# Weatstone_bridges_part_II.net
KiCad netlist of a schematic drawn in Altium Designer
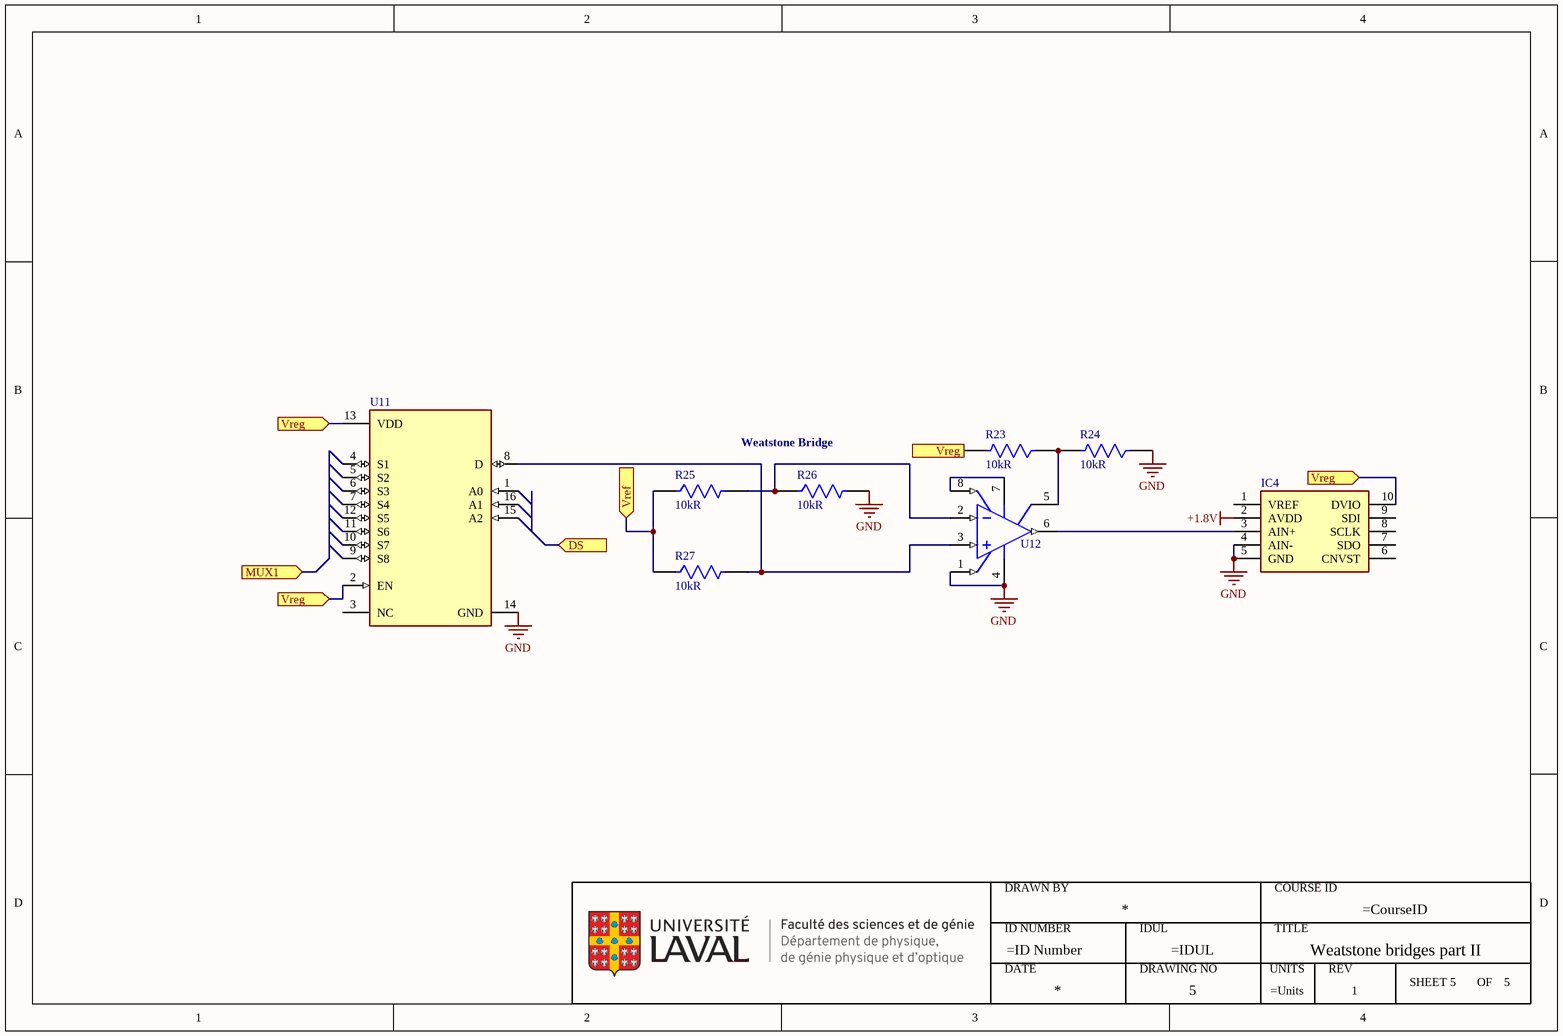
[diagram p0: Weatstone bridges part II.SchDoc]

(export (version "E")
  (design (tool "Eeschema 10.0.6"))
  (components
    (comp (ref "*4")
      (value "ULaval FSG-DPGPO")
      (libsource (lib "ULaval Title Block") (part "ULaval FSG-DPGPO"))
    )
    (comp (ref "IC4")
      (value "MCP33141-10-E_MS")
      (footprint "SamacSys:SOP50P490X110-10N")
      (description "Integrated Circuit")
      (fields
        (field (name "MANUFACTURER_PART_NUMBER") "MCP33141-10-E/MS")
        (field (name "MOUSER PART NUMBER") "579-MCP33141-10-E/MS")
      )
      (libsource (lib "SamacSys") (part "MCP33141-10-E_MS"))
    )
    (comp (ref "R23")
      (value "10kR")
      (footprint "FP-RT0603-IPC_C")
      (description "Res High precision Thin Film 0603 10K Ohm 0.1% 1/10W ±25ppm/°C Molded SMD Paper T/R")
      (fields (field (name "Comment") "RT0603BRD0710KL"))
      (libsource (lib "Laval University") (part "1029c3af85768c4190bb7ad29bc67b5"))
    )
    (comp (ref "R24")
      (value "10kR")
      (footprint "FP-RT0603-IPC_C")
      (description "Res High precision Thin Film 0603 10K Ohm 0.1% 1/10W ±25ppm/°C Molded SMD Paper T/R")
      (fields (field (name "Comment") "RT0603BRD0710KL"))
      (libsource (lib "Laval University") (part "1029c3af85768c4190bb7ad29bc67b5"))
    )
    (comp (ref "R25")
      (value "10kR")
      (footprint "FP-RT0603-IPC_C")
      (description "Res High precision Thin Film 0603 10K Ohm 0.1% 1/10W ±25ppm/°C Molded SMD Paper T/R")
      (fields (field (name "Comment") "RT0603BRD0710KL"))
      (libsource (lib "Laval University") (part "1029c3af85768c4190bb7ad29bc67b5"))
    )
    (comp (ref "R26")
      (value "10kR")
      (footprint "FP-RT0603-IPC_C")
      (description "Res High precision Thin Film 0603 10K Ohm 0.1% 1/10W ±25ppm/°C Molded SMD Paper T/R")
      (fields (field (name "Comment") "RT0603BRD0710KL"))
      (libsource (lib "Laval University") (part "1029c3af85768c4190bb7ad29bc67b5"))
    )
    (comp (ref "R27")
      (value "10kR")
      (footprint "FP-RT0603-IPC_C")
      (description "Res High precision Thin Film 0603 10K Ohm 0.1% 1/10W ±25ppm/°C Molded SMD Paper T/R")
      (fields (field (name "Comment") "RT0603BRD0710KL"))
      (libsource (lib "Laval University") (part "1029c3af85768c4190bb7ad29bc67b5"))
    )
    (comp (ref "U11")
      (value "TMUX1208PWR")
      (footprint "FP-PW0016A-IPC_B")
      (description "5-V, 8: 1, 1-channel general-purpose analog multiplexer with 1.8-V input logic 16-TSSOP -40 to 125")
      (libsource (lib "Laval University") (part "3fc1eebd4caa5623a46538ca285a60d"))
    )
    (comp (ref "U12")
      (value "MCP6N11-100E/SN")
      (footprint "SOIC-SN8_L")
      (description "MCP6N11 Series Single Channel 500 KHz 5.5 V Instrumentation Amplifier - SOIC-8")
      (libsource (lib "Laval University") (part "AMP-INA-MCP6N11-IL8"))
    )
  )
  (nets
    (net (code "1") (name "+1.8V") (class "Default")
      (node (ref "IC4") (pin "2") (pinfunction "AVDD_2") (pintype "passive"))
    )
    (net (code "4") (name "/Vref") (class "Default")
      (node (ref "R25") (pin "1") (pinfunction "1_1") (pintype "passive"))
      (node (ref "R27") (pin "1") (pinfunction "1_1") (pintype "passive"))
    )
    (net (code "5") (name "/Vreg") (class "Default")
      (node (ref "IC4") (pin "10") (pinfunction "DVIO_10") (pintype "passive"))
      (node (ref "R23") (pin "2") (pinfunction "2_2") (pintype "passive"))
      (node (ref "U11") (pin "13") (pinfunction "VDD_13") (pintype "power_in"))
      (node (ref "U11") (pin "2") (pinfunction "EN_2") (pintype "input"))
    )
    (net (code "6") (name "GND") (class "Default")
      (node (ref "IC4") (pin "4") (pinfunction "AIN-_4") (pintype "passive"))
      (node (ref "IC4") (pin "5") (pinfunction "GND_5") (pintype "passive"))
      (node (ref "R24") (pin "1") (pinfunction "1_1") (pintype "passive"))
      (node (ref "R26") (pin "2") (pinfunction "2_2") (pintype "passive"))
      (node (ref "U11") (pin "14") (pinfunction "GND_14") (pintype "power_in"))
      (node (ref "U12") (pin "1") (pinfunction "VFG_1") (pintype "input"))
      (node (ref "U12") (pin "4") (pinfunction "VSS_4") (pintype "power_in"))
    )
    (net (code "7") (name "Net-(IC4-AIN+)") (class "Default")
      (node (ref "IC4") (pin "3") (pinfunction "AIN+_3") (pintype "passive"))
      (node (ref "U12") (pin "6") (pinfunction "VOUT_6") (pintype "output"))
    )
    (net (code "8") (name "Net-(U11-D)") (class "Default")
      (node (ref "R27") (pin "2") (pinfunction "2_2") (pintype "passive"))
      (node (ref "U11") (pin "8") (pinfunction "D_8") (pintype "bidirectional"))
      (node (ref "U12") (pin "3") (pinfunction "VIP_3") (pintype "input"))
    )
    (net (code "9") (name "Net-(U12-EN{slash}~{CAL})") (class "Default")
      (node (ref "U12") (pin "7") (pinfunction "VDD_7") (pintype "power_in"))
      (node (ref "U12") (pin "8") (pinfunction "EN/~{CAL}_8") (pintype "input"))
    )
    (net (code "10") (name "Net-(U12-VIM)") (class "Default")
      (node (ref "R25") (pin "2") (pinfunction "2_2") (pintype "passive"))
      (node (ref "R26") (pin "1") (pinfunction "1_1") (pintype "passive"))
      (node (ref "U12") (pin "2") (pinfunction "VIM_2") (pintype "input"))
    )
    (net (code "11") (name "Net-(U12-VREF)") (class "Default")
      (node (ref "R23") (pin "1") (pinfunction "1_1") (pintype "passive"))
      (node (ref "R24") (pin "2") (pinfunction "2_2") (pintype "passive"))
      (node (ref "U12") (pin "5") (pinfunction "VREF_5") (pintype "power_in"))
    )
    (net (code "12") (name "unconnected-(IC4-CNVST-Pad6)") (class "Default")
      (node (ref "IC4") (pin "6") (pinfunction "CNVST_6") (pintype "passive"))
    )
    (net (code "13") (name "unconnected-(IC4-SCLK-Pad8)") (class "Default")
      (node (ref "IC4") (pin "8") (pinfunction "SCLK_8") (pintype "passive"))
    )
    (net (code "14") (name "unconnected-(IC4-SDI-Pad9)") (class "Default")
      (node (ref "IC4") (pin "9") (pinfunction "SDI_9") (pintype "passive"))
    )
    (net (code "15") (name "unconnected-(IC4-SDO-Pad7)") (class "Default")
      (node (ref "IC4") (pin "7") (pinfunction "SDO_7") (pintype "passive"))
    )
    (net (code "16") (name "unconnected-(IC4-VREF-Pad1)") (class "Default")
      (node (ref "IC4") (pin "1") (pinfunction "VREF_1") (pintype "passive"))
    )
    (net (code "17") (name "unconnected-(U11-A0-Pad1)") (class "Default")
      (node (ref "U11") (pin "1") (pinfunction "A0_1") (pintype "input"))
    )
    (net (code "18") (name "unconnected-(U11-A1-Pad16)") (class "Default")
      (node (ref "U11") (pin "16") (pinfunction "A1_16") (pintype "input"))
    )
    (net (code "19") (name "unconnected-(U11-A2-Pad15)") (class "Default")
      (node (ref "U11") (pin "15") (pinfunction "A2_15") (pintype "input"))
    )
    (net (code "20") (name "unconnected-(U11-NC-Pad3)") (class "Default")
      (node (ref "U11") (pin "3") (pinfunction "NC_3") (pintype "passive"))
    )
    (net (code "21") (name "unconnected-(U11-S1-Pad4)") (class "Default")
      (node (ref "U11") (pin "4") (pinfunction "S1_4") (pintype "bidirectional"))
    )
    (net (code "22") (name "unconnected-(U11-S2-Pad5)") (class "Default")
      (node (ref "U11") (pin "5") (pinfunction "S2_5") (pintype "bidirectional"))
    )
    (net (code "23") (name "unconnected-(U11-S3-Pad6)") (class "Default")
      (node (ref "U11") (pin "6") (pinfunction "S3_6") (pintype "bidirectional"))
    )
    (net (code "24") (name "unconnected-(U11-S4-Pad7)") (class "Default")
      (node (ref "U11") (pin "7") (pinfunction "S4_7") (pintype "bidirectional"))
    )
    (net (code "25") (name "unconnected-(U11-S5-Pad12)") (class "Default")
      (node (ref "U11") (pin "12") (pinfunction "S5_12") (pintype "bidirectional"))
    )
    (net (code "26") (name "unconnected-(U11-S6-Pad11)") (class "Default")
      (node (ref "U11") (pin "11") (pinfunction "S6_11") (pintype "bidirectional"))
    )
    (net (code "27") (name "unconnected-(U11-S7-Pad10)") (class "Default")
      (node (ref "U11") (pin "10") (pinfunction "S7_10") (pintype "bidirectional"))
    )
    (net (code "28") (name "unconnected-(U11-S8-Pad9)") (class "Default")
      (node (ref "U11") (pin "9") (pinfunction "S8_9") (pintype "bidirectional"))
    )
  )
)
